# TPS75501_2V5.net
KiCad netlist of a schematic drawn in Altium Designer
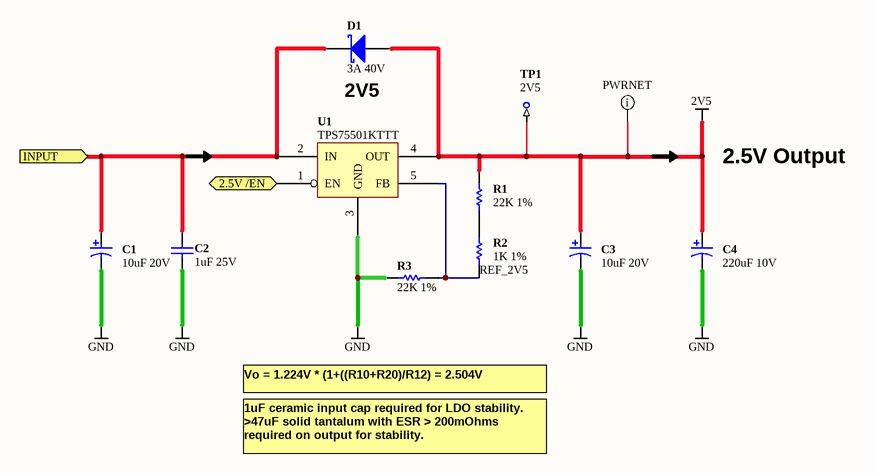
[diagram p0: TPS75501_2V5.SchDoc]

(export (version "E")
  (design (tool "Eeschema 10.0.6"))
  (components
    (comp (ref "C1")
      (value "10uF 20V")
      (footprint "CAPC3528-STAR")
      (description "Capacitor, Tantalum, 10uF 10% 20V MCCT-B (3528)")
      (fields (field (name "TOLERANCE") "10 %"))
      (libsource (lib "altium-import") (part "root_0_CAP-P_"))
    )
    (comp (ref "C2")
      (value "1uF 25V")
      (footprint "CAPC3216-STAR")
      (description "Capacitor, Ceramic, 1uF 10% 25V 1206 (3216) X7R")
      (fields (field (name "TOLERANCE") "10 %"))
      (libsource (lib "altium-import") (part "root_0_CAP-NP_"))
    )
    (comp (ref "C3")
      (value "10uF 20V")
      (footprint "CAPC3528-STAR")
      (description "Capacitor, Tantalum, 10uF 10% 20V MCCT-B (3528)")
      (fields (field (name "TOLERANCE") "10 %"))
      (libsource (lib "altium-import") (part "root_0_CAP-P_"))
    )
    (comp (ref "C4")
      (value "220uF 10V")
      (footprint "CAPC7343-STAR")
      (description "Capacitor, Tantalum, 220uF 10% 10V MCCT-D (7343-31)")
      (fields (field (name "TOLERANCE") "10 %"))
      (libsource (lib "altium-import") (part "root_0_CAP-P_"))
    )
    (comp (ref "D1")
      (value "3A 40V")
      (footprint "DIOM5027")
      (description "Schottky Diode, 3A 40V")
      (libsource (lib "altium-import") (part "root_2_DIO-SCHOTTKY-1S_"))
    )
    (comp (ref "R1")
      (value "22K 1%")
      (footprint "RESC1005-STAR")
      (description "Resistor, 22K 1% 0402 (1005)")
      (fields (field (name "TOLERANCE") "1 %"))
      (libsource (lib "altium-import") (part "root_2_RES_"))
    )
    (comp (ref "R2")
      (value "1K 1%")
      (footprint "RESC1005-STAR")
      (description "Resistor, 1K 1% 0402 (1005)")
      (fields (field (name "TOLERANCE") "1 %"))
      (libsource (lib "altium-import") (part "root_0_RES_"))
    )
    (comp (ref "R3")
      (value "22K 1%")
      (footprint "RESC1005-STAR")
      (description "Resistor, 22K 1% 0402 (1005)")
      (fields (field (name "TOLERANCE") "1 %"))
      (libsource (lib "altium-import") (part "root_3_RES_"))
    )
    (comp (ref "TP1")
      (value "2V5")
      (footprint "TestPin")
      (description "Test Point, PCB Mount with Silkscreen Box")
      (libsource (lib "AltiumDesignLibrary") (part "TestPin"))
    )
    (comp (ref "U1")
      (value "TPS75501KTTT")
      (footprint "TO-263")
      (description "TPS75501KTTT, 5A, Low Dropout, Adjustable, Linear Voltage Regulator, TO-263")
      (libsource (lib "altium-import") (part "root_0_TPS75501_"))
    )
  )
  (nets
    (net (code "1") (name "/2.5V {slash}EN") (class "Default")
      (node (ref "U1") (pin "1") (pinfunction "EN_1") (pintype "passive"))
    )
    (net (code "2") (name "/INPUT") (class "Default")
      (node (ref "C1") (pin "1") (pinfunction "1_1") (pintype "passive"))
      (node (ref "C2") (pin "1") (pinfunction "1_1") (pintype "passive"))
      (node (ref "D1") (pin "2") (pinfunction "K_2") (pintype "passive"))
      (node (ref "U1") (pin "2") (pinfunction "IN_2") (pintype "passive"))
    )
    (net (code "3") (name "/REF_2V5") (class "Default")
      (node (ref "R2") (pin "2") (pinfunction "2_2") (pintype "passive"))
      (node (ref "R3") (pin "1") (pinfunction "1_1") (pintype "passive"))
      (node (ref "U1") (pin "5") (pinfunction "FB_5") (pintype "passive"))
    )
    (net (code "4") (name "2V5") (class "Default")
      (node (ref "C3") (pin "1") (pinfunction "1_1") (pintype "passive"))
      (node (ref "C4") (pin "1") (pinfunction "1_1") (pintype "passive"))
      (node (ref "D1") (pin "1") (pinfunction "A_1") (pintype "passive"))
      (node (ref "R1") (pin "2") (pinfunction "2_2") (pintype "passive"))
      (node (ref "TP1") (pin "1") (pinfunction "1_1") (pintype "input"))
      (node (ref "U1") (pin "4") (pinfunction "OUT_4") (pintype "passive"))
    )
    (net (code "5") (name "GND") (class "Default")
      (node (ref "C1") (pin "2") (pinfunction "2_2") (pintype "passive"))
      (node (ref "C2") (pin "2") (pinfunction "2_2") (pintype "passive"))
      (node (ref "C3") (pin "2") (pinfunction "2_2") (pintype "passive"))
      (node (ref "C4") (pin "2") (pinfunction "2_2") (pintype "passive"))
      (node (ref "R3") (pin "2") (pinfunction "2_2") (pintype "passive"))
      (node (ref "U1") (pin "3") (pinfunction "GND_3") (pintype "passive"))
    )
    (net (code "6") (name "Net-(R1-Pad1)") (class "Default")
      (node (ref "R1") (pin "1") (pinfunction "1_1") (pintype "passive"))
      (node (ref "R2") (pin "1") (pinfunction "1_1") (pintype "passive"))
    )
  )
)
